# STLink_V3E_Module.net
KiCad netlist of a schematic drawn in Altium Designer
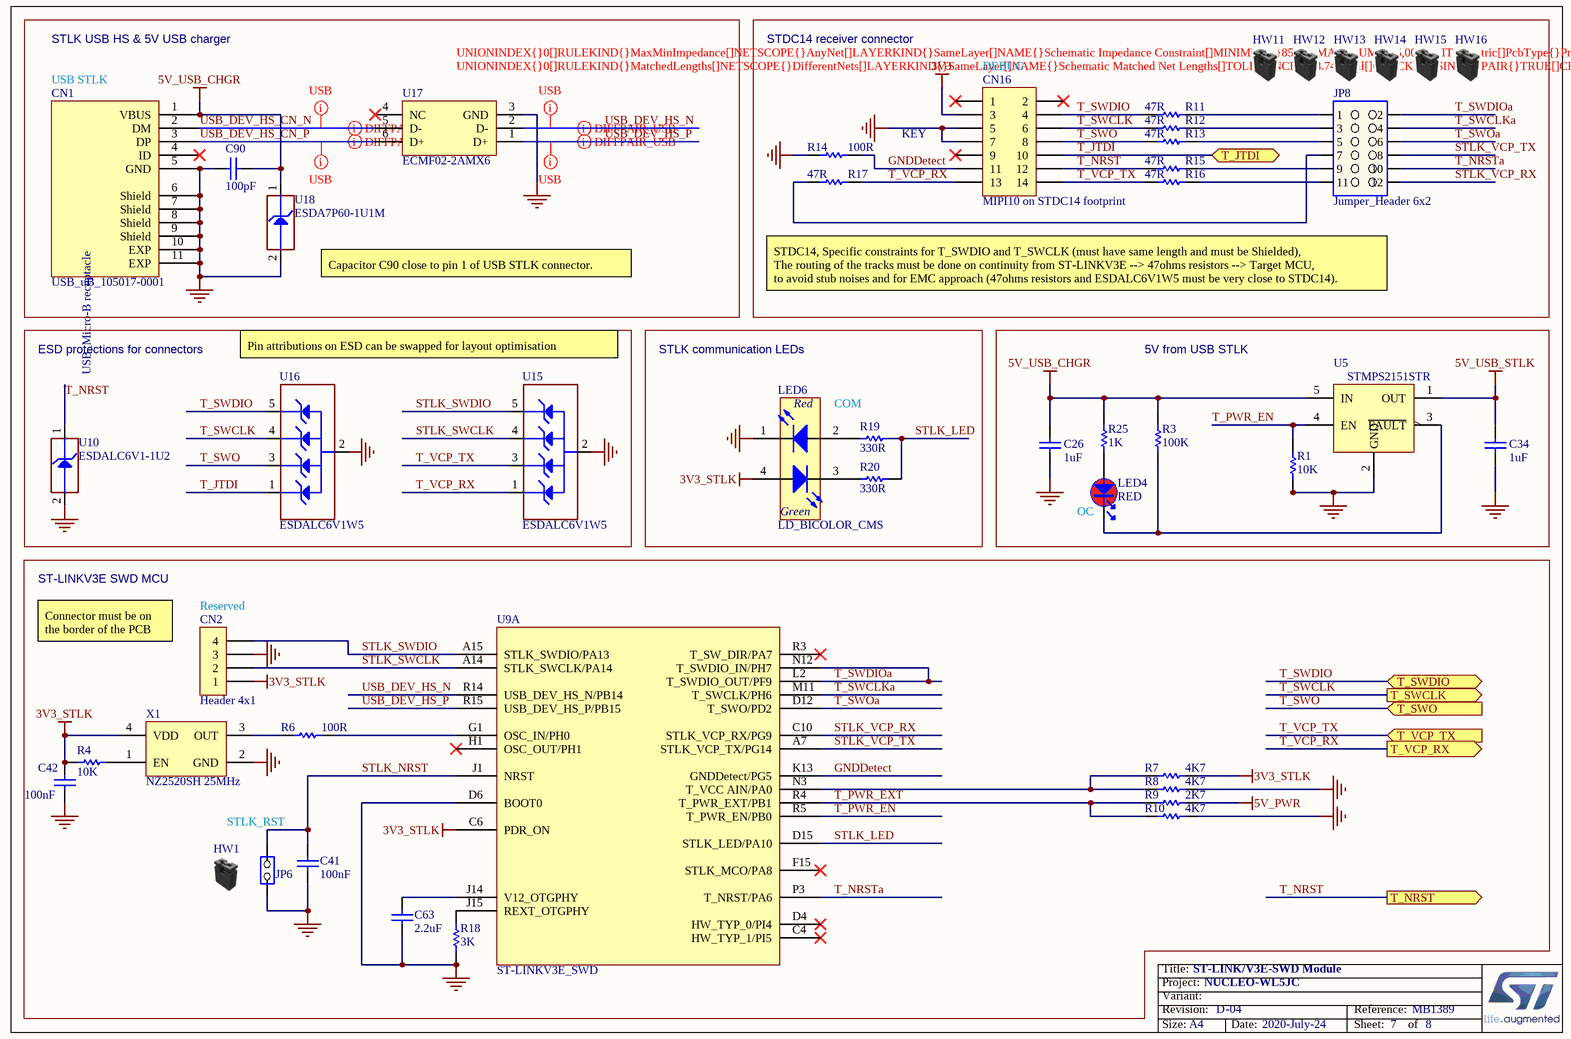
[diagram p0: STLink_V3E_Module.SchDoc]

(export (version "E")
  (design (tool "Eeschema 10.0.6"))
  (components
    (comp (ref "C26")
      (value "1uF")
      (footprint "C0603")
      (description "Capacitor, MLCC, 1uF, 16V, X5R, 10%, 0603, T=0,8mm")
      (fields
        (field (name "INTERNAL_PART_NUMBER") "MCD-00010")
        (field (name "MANUFACTURER_PART_NUMBER") "CC0603KRX5R7BB105")
        (field (name "PROVIDED_BY") "SUBCO")
      )
      (libsource (lib "MCD_PARTS_database") (part "Capacitor"))
    )
    (comp (ref "C34")
      (value "1uF")
      (footprint "C0603")
      (description "Capacitor, MLCC, 1uF, 16V, X5R, 10%, 0603, T=0,8mm")
      (fields
        (field (name "INTERNAL_PART_NUMBER") "MCD-00010")
        (field (name "MANUFACTURER_PART_NUMBER") "CC0603KRX5R7BB105")
        (field (name "PROVIDED_BY") "SUBCO")
      )
      (libsource (lib "MCD_PARTS_database") (part "Capacitor"))
    )
    (comp (ref "C41")
      (value "100nF")
      (footprint "C0402")
      (description "Capacitor, MLCC, 100nF, 16V, X7R, 10%, 0402, T=0,5mm")
      (fields
        (field (name "INTERNAL_PART_NUMBER") "MCD-00102")
        (field (name "MANUFACTURER_PART_NUMBER") "CC0402KRX7R7BB104")
        (field (name "PROVIDED_BY") "SUBCO")
      )
      (libsource (lib "MCD_PARTS_database") (part "Capacitor"))
    )
    (comp (ref "C42")
      (value "100nF")
      (footprint "C0402")
      (description "Capacitor, MLCC, 100nF, 16V, X7R, 10%, 0402, T=0,5mm")
      (fields
        (field (name "INTERNAL_PART_NUMBER") "MCD-00102")
        (field (name "MANUFACTURER_PART_NUMBER") "CC0402KRX7R7BB104")
        (field (name "PROVIDED_BY") "SUBCO")
      )
      (libsource (lib "MCD_PARTS_database") (part "Capacitor"))
    )
    (comp (ref "C63")
      (value "2.2uF")
      (footprint "C0603")
      (description "Capacitor, MLCC, 2.2uF, 10V, X5R, 10%, 0603, T=0,8mm")
      (fields
        (field (name "INTERNAL_PART_NUMBER") "MCD-00012")
        (field (name "MANUFACTURER_PART_NUMBER") "CC0603KRX5R6BB225")
        (field (name "PROVIDED_BY") "SUBCO")
      )
      (libsource (lib "MCD_PARTS_database") (part "Capacitor"))
    )
    (comp (ref "C90")
      (value "100pF")
      (footprint "C0402")
      (description "Capacitor, MLCC, 100pF, 50V, NPO, 5%, 0402, T=0,5mm")
      (fields
        (field (name "INTERNAL_PART_NUMBER") "MCD-00205")
        (field (name "MANUFACTURER_PART_NUMBER") "CC0402JRNPO9BN101")
        (field (name "PROVIDED_BY") "SUBCO")
      )
      (libsource (lib "MCD_PARTS_database") (part "Capacitor"))
    )
    (comp (ref "CN1")
      (value "USB_uB_105017-0001")
      (footprint "CON_USBMICROB_MOLEX_105017-0001_H2P90")
      (description "USB-MICRO-B, 0.65mm, RA, SMT, Bottom Mount,")
      (fields
        (field (name "INTERNAL_PART_NUMBER") "MCD-00028")
        (field (name "MANUFACTURER_PART_NUMBER") "1050170001")
        (field (name "PROVIDED_BY") "SUBCO")
      )
      (libsource (lib "MCD_PARTS_database") (part "USB_uB_105017.0001"))
    )
    (comp (ref "CN2")
      (value "Header 4x1")
      (footprint "CON_SAMTEC_TSW-104-07-G-S")
      (description "Header, 4x1, 2,54mm, VR, TH, Height 5.84mm/2.54mm")
      (fields
        (field (name "INTERNAL_PART_NUMBER") "MCD-00029")
        (field (name "MANUFACTURER_PART_NUMBER") "TSW-104-07-x-S")
        (field (name "PROVIDED_BY") "SUBCO")
      )
      (libsource (lib "MCD_PARTS_database") (part "Header 4x1"))
    )
    (comp (ref "CN16")
      (value "MIPI10 on STDC14 footprint")
      (footprint "CON_STDC14_Receiver_MEDIUM_WITH_MIPI10_3D")
      (fields
        (field (name "INTERNAL_PART_NUMBER") "MCD-01226")
        (field (name "MANUFACTURER_PART_NUMBER") "FTSH-105-01-L-DV-K")
        (field (name "MANUFACTURER") "SAMTEC")
        (field (name "PROVIDED_BY") "SUBCO")
      )
      (libsource (lib "MCD_PARTS_database") (part "Header 7x2"))
    )
    (comp (ref "HW1")
      (value "~")
      (description "SHUNT 2.54mm BLACK")
      (fields
        (field (name "INTERNAL_PART_NUMBER") "MCD-00043")
        (field (name "MANUFACTURER_PART_NUMBER") "SNT-100-BK-G")
        (field (name "PROVIDED_BY") "SUBCO")
      )
      (libsource (lib "MCD_PARTS_database") (part "Shunt Black 2.54mm"))
    )
    (comp (ref "HW11")
      (value "~")
      (description "SHUNT 2.54mm BLACK")
      (fields
        (field (name "INTERNAL_PART_NUMBER") "MCD-00043")
        (field (name "MANUFACTURER_PART_NUMBER") "SNT-100-BK-G")
        (field (name "PROVIDED_BY") "SUBCO")
      )
      (libsource (lib "MCD_PARTS_database") (part "Shunt Black 2.54mm"))
    )
    (comp (ref "HW12")
      (value "~")
      (description "SHUNT 2.54mm BLACK")
      (fields
        (field (name "INTERNAL_PART_NUMBER") "MCD-00043")
        (field (name "MANUFACTURER_PART_NUMBER") "SNT-100-BK-G")
        (field (name "PROVIDED_BY") "SUBCO")
      )
      (libsource (lib "MCD_PARTS_database") (part "Shunt Black 2.54mm"))
    )
    (comp (ref "HW13")
      (value "~")
      (description "SHUNT 2.54mm BLACK")
      (fields
        (field (name "INTERNAL_PART_NUMBER") "MCD-00043")
        (field (name "MANUFACTURER_PART_NUMBER") "SNT-100-BK-G")
        (field (name "PROVIDED_BY") "SUBCO")
      )
      (libsource (lib "MCD_PARTS_database") (part "Shunt Black 2.54mm"))
    )
    (comp (ref "HW14")
      (value "~")
      (description "SHUNT 2.54mm BLACK")
      (fields
        (field (name "INTERNAL_PART_NUMBER") "MCD-00043")
        (field (name "MANUFACTURER_PART_NUMBER") "SNT-100-BK-G")
        (field (name "PROVIDED_BY") "SUBCO")
      )
      (libsource (lib "MCD_PARTS_database") (part "Shunt Black 2.54mm"))
    )
    (comp (ref "HW15")
      (value "~")
      (description "SHUNT 2.54mm BLACK")
      (fields
        (field (name "INTERNAL_PART_NUMBER") "MCD-00043")
        (field (name "MANUFACTURER_PART_NUMBER") "SNT-100-BK-G")
        (field (name "PROVIDED_BY") "SUBCO")
      )
      (libsource (lib "MCD_PARTS_database") (part "Shunt Black 2.54mm"))
    )
    (comp (ref "HW16")
      (value "~")
      (description "SHUNT 2.54mm BLACK")
      (fields
        (field (name "INTERNAL_PART_NUMBER") "MCD-00043")
        (field (name "MANUFACTURER_PART_NUMBER") "SNT-100-BK-G")
        (field (name "PROVIDED_BY") "SUBCO")
      )
      (libsource (lib "MCD_PARTS_database") (part "Shunt Black 2.54mm"))
    )
    (comp (ref "JP6")
      (value "~")
      (footprint "CON_SAMTEC_TSW-102-07-G-S")
      (description "Header, 2x1, 2,54mm, VR, TH, Height 5.84mm/2.54mm")
      (fields
        (field (name "INTERNAL_PART_NUMBER") "MCD-00045")
        (field (name "MANUFACTURER_PART_NUMBER") "TSW-102-07-G-S")
        (field (name "PROVIDED_BY") "SUBCO")
      )
      (libsource (lib "MCD_PARTS_database") (part "Jumper_Header 2x1"))
    )
    (comp (ref "JP8")
      (value "Jumper_Header 6x2")
      (footprint "CON_SAMTEC_TSW-106-07-X-D")
      (description "Header, 6x2, 2,54mm, VR, TH, Height 5.84mm/2.54mm")
      (fields
        (field (name "INTERNAL_PART_NUMBER") "MCD-00692")
        (field (name "MANUFACTURER_PART_NUMBER") "TSW-106-07-x-D")
        (field (name "PROVIDED_BY") "SUBCO")
      )
      (libsource (lib "MCD_PARTS_database") (part "Jumper_Header 6x2"))
    )
    (comp (ref "LED4")
      (value "RED")
      (footprint "LED_0603_VISHAY_VLMS1300-GS08_RED_1A2K_H0P8")
      (description "LED Red, 0603 SMD, 2V Forward Voltage")
      (fields
        (field (name "INTERNAL_PART_NUMBER") "MCD-00587")
        (field (name "MANUFACTURER_PART_NUMBER") "VLMS1300-GS08")
        (field (name "PROVIDED_BY") "SUBCO")
      )
      (libsource (lib "MCD_PARTS_database") (part "LED_red"))
    )
    (comp (ref "LED6")
      (value "LD_BICOLOR_CMS")
      (footprint "LED_BI-GR_HSMF-A201-A00J1")
      (description "LED Bicolor")
      (fields
        (field (name "INTERNAL_PART_NUMBER") "MCD-00051")
        (field (name "MANUFACTURER_PART_NUMBER") "HSMF-A201-A00J1")
        (field (name "PROVIDED_BY") "SUBCO")
      )
      (libsource (lib "MCD_PARTS_database") (part "LD_BICOLOR_CMS"))
    )
    (comp (ref "R1")
      (value "10K")
      (footprint "R0402")
      (description "Resistor,10K,0402,1%,1/16W")
      (fields
        (field (name "INTERNAL_PART_NUMBER") "MCD-00053")
        (field (name "MANUFACTURER_PART_NUMBER") "RC0402FR-0710KL")
        (field (name "PROVIDED_BY") "SUBCO")
      )
      (libsource (lib "MCD_PARTS_database") (part "Resistor"))
    )
    (comp (ref "R3")
      (value "100K")
      (footprint "R0402")
      (description "Resistor,100K,0402,1%,1/16W")
      (fields
        (field (name "INTERNAL_PART_NUMBER") "MCD-00059")
        (field (name "MANUFACTURER_PART_NUMBER") "RC0402FR-07100KL")
        (field (name "PROVIDED_BY") "SUBCO")
      )
      (libsource (lib "MCD_PARTS_database") (part "Resistor"))
    )
    (comp (ref "R4")
      (value "10K")
      (footprint "R0402")
      (description "Resistor,10K,0402,1%,1/16W")
      (fields
        (field (name "INTERNAL_PART_NUMBER") "MCD-00053")
        (field (name "MANUFACTURER_PART_NUMBER") "RC0402FR-0710KL")
        (field (name "PROVIDED_BY") "SUBCO")
      )
      (libsource (lib "MCD_PARTS_database") (part "Resistor"))
    )
    (comp (ref "R6")
      (value "100R")
      (footprint "R0402")
      (description "Resistor,100R,0402,1%,1/16W")
      (fields
        (field (name "INTERNAL_PART_NUMBER") "MCD-00119")
        (field (name "MANUFACTURER_PART_NUMBER") "RC0402FR-07100RL")
        (field (name "PROVIDED_BY") "SUBCO")
      )
      (libsource (lib "MCD_PARTS_database") (part "Resistor"))
    )
    (comp (ref "R7")
      (value "4K7")
      (footprint "R0402")
      (description "Resistor,4K7,0402,1%,1/16W")
      (fields
        (field (name "INTERNAL_PART_NUMBER") "MCD-00065")
        (field (name "MANUFACTURER_PART_NUMBER") "RC0402FR-074K7L")
        (field (name "PROVIDED_BY") "SUBCO")
      )
      (libsource (lib "MCD_PARTS_database") (part "Resistor"))
    )
    (comp (ref "R8")
      (value "4K7")
      (footprint "R0402")
      (description "Resistor,4K7,0402,1%,1/16W")
      (fields
        (field (name "INTERNAL_PART_NUMBER") "MCD-00065")
        (field (name "MANUFACTURER_PART_NUMBER") "RC0402FR-074K7L")
        (field (name "PROVIDED_BY") "SUBCO")
      )
      (libsource (lib "MCD_PARTS_database") (part "Resistor"))
    )
    (comp (ref "R9")
      (value "2K7")
      (footprint "R0402")
      (description "Resistor,2K7,0402,1%,1/16W")
      (fields
        (field (name "INTERNAL_PART_NUMBER") "MCD-00055")
        (field (name "MANUFACTURER_PART_NUMBER") "RC0402FR-072K7L")
        (field (name "PROVIDED_BY") "SUBCO")
      )
      (libsource (lib "MCD_PARTS_database") (part "Resistor"))
    )
    (comp (ref "R10")
      (value "4K7")
      (footprint "R0402")
      (description "Resistor,4K7,0402,1%,1/16W")
      (fields
        (field (name "INTERNAL_PART_NUMBER") "MCD-00065")
        (field (name "MANUFACTURER_PART_NUMBER") "RC0402FR-074K7L")
        (field (name "PROVIDED_BY") "SUBCO")
      )
      (libsource (lib "MCD_PARTS_database") (part "Resistor"))
    )
    (comp (ref "R11")
      (value "47R")
      (footprint "R0402")
      (description "Resistor,47R,0402,1%,1/16W")
      (fields
        (field (name "INTERNAL_PART_NUMBER") "MCD-00481")
        (field (name "MANUFACTURER_PART_NUMBER") "RC0402FR-0747RL")
        (field (name "PROVIDED_BY") "SUBCO")
      )
      (libsource (lib "MCD_PARTS_database") (part "Resistor"))
    )
    (comp (ref "R12")
      (value "47R")
      (footprint "R0402")
      (description "Resistor,47R,0402,1%,1/16W")
      (fields
        (field (name "INTERNAL_PART_NUMBER") "MCD-00481")
        (field (name "MANUFACTURER_PART_NUMBER") "RC0402FR-0747RL")
        (field (name "PROVIDED_BY") "SUBCO")
      )
      (libsource (lib "MCD_PARTS_database") (part "Resistor"))
    )
    (comp (ref "R13")
      (value "47R")
      (footprint "R0402")
      (description "Resistor,47R,0402,1%,1/16W")
      (fields
        (field (name "INTERNAL_PART_NUMBER") "MCD-00481")
        (field (name "MANUFACTURER_PART_NUMBER") "RC0402FR-0747RL")
        (field (name "PROVIDED_BY") "SUBCO")
      )
      (libsource (lib "MCD_PARTS_database") (part "Resistor"))
    )
    (comp (ref "R14")
      (value "100R")
      (footprint "R0402")
      (description "Resistor,100R,0402,1%,1/16W")
      (fields
        (field (name "INTERNAL_PART_NUMBER") "MCD-00119")
        (field (name "MANUFACTURER_PART_NUMBER") "RC0402FR-07100RL")
        (field (name "PROVIDED_BY") "SUBCO")
      )
      (libsource (lib "MCD_PARTS_database") (part "Resistor"))
    )
    (comp (ref "R15")
      (value "47R")
      (footprint "R0402")
      (description "Resistor,47R,0402,1%,1/16W")
      (fields
        (field (name "INTERNAL_PART_NUMBER") "MCD-00481")
        (field (name "MANUFACTURER_PART_NUMBER") "RC0402FR-0747RL")
        (field (name "PROVIDED_BY") "SUBCO")
      )
      (libsource (lib "MCD_PARTS_database") (part "Resistor"))
    )
    (comp (ref "R16")
      (value "47R")
      (footprint "R0402")
      (description "Resistor,47R,0402,1%,1/16W")
      (fields
        (field (name "INTERNAL_PART_NUMBER") "MCD-00481")
        (field (name "MANUFACTURER_PART_NUMBER") "RC0402FR-0747RL")
        (field (name "PROVIDED_BY") "SUBCO")
      )
      (libsource (lib "MCD_PARTS_database") (part "Resistor"))
    )
    (comp (ref "R17")
      (value "47R")
      (footprint "R0402")
      (description "Resistor,47R,0402,1%,1/16W")
      (fields
        (field (name "INTERNAL_PART_NUMBER") "MCD-00481")
        (field (name "MANUFACTURER_PART_NUMBER") "RC0402FR-0747RL")
        (field (name "PROVIDED_BY") "SUBCO")
      )
      (libsource (lib "MCD_PARTS_database") (part "Resistor"))
    )
    (comp (ref "R18")
      (value "3K")
      (footprint "R0402")
      (description "Resistor,3K,0402,1%,1/16W")
      (fields
        (field (name "INTERNAL_PART_NUMBER") "MCD-00185")
        (field (name "MANUFACTURER_PART_NUMBER") "RC0402FR-073KL")
        (field (name "PROVIDED_BY") "SUBCO")
      )
      (libsource (lib "MCD_PARTS_database") (part "Resistor"))
    )
    (comp (ref "R19")
      (value "330R")
      (footprint "R0603")
      (description "Resistor,330R,0603,1%,1/10W")
      (fields
        (field (name "INTERNAL_PART_NUMBER") "MCD-00197")
        (field (name "MANUFACTURER_PART_NUMBER") "RC0603FR-07330RL")
        (field (name "PROVIDED_BY") "SUBCO")
      )
      (libsource (lib "MCD_PARTS_database") (part "Resistor"))
    )
    (comp (ref "R20")
      (value "330R")
      (footprint "R0603")
      (description "Resistor,330R,0603,1%,1/10W")
      (fields
        (field (name "INTERNAL_PART_NUMBER") "MCD-00197")
        (field (name "MANUFACTURER_PART_NUMBER") "RC0603FR-07330RL")
        (field (name "PROVIDED_BY") "SUBCO")
      )
      (libsource (lib "MCD_PARTS_database") (part "Resistor"))
    )
    (comp (ref "R25")
      (value "1K")
      (footprint "R0603")
      (description "Resistor,1K,0603,1%,1/10W")
      (fields
        (field (name "INTERNAL_PART_NUMBER") "MCD-00070")
        (field (name "MANUFACTURER_PART_NUMBER") "RC0603FR-071KL")
        (field (name "PROVIDED_BY") "SUBCO")
      )
      (libsource (lib "MCD_PARTS_database") (part "Resistor"))
    )
    (comp (ref "U5")
      (value "STMPS2151STR")
      (footprint "MOS_SOT23-5L")
      (description "500mA, Enhanced single channel power switches with active high enable pin")
      (fields
        (field (name "INTERNAL_PART_NUMBER") "MCD-00159")
        (field (name "MANUFACTURER") "STMICROELECTRONICS")
        (field (name "PROVIDED_BY") "SUBCO with ST control")
      )
      (libsource (lib "MCD_PARTS_database") (part "STMPS2151STR"))
    )
    (comp (ref "U9")
      (value "ST-LINKV3E_SWD")
      (footprint "ICC_UFBGA201_176+25_10X10_P065")
      (description "STM32F723IEK  (STM32F7) BGA176")
      (fields
        (field (name "INTERNAL_PART_NUMBER") "MCD-00596")
        (field (name "MANUFACTURER_PART_NUMBER") "STM32F723IEK6")
        (field (name "PROVIDED_BY") "SUBCO with ST control")
      )
      (libsource (lib "MCD_PARTS_database") (part "ST-LINKV3E_SWD"))
    )
    (comp (ref "U10")
      (value "ESDALC6V1-1U2")
      (footprint "ESD_ST0201")
      (description "ESD protection 6V1")
      (fields
        (field (name "INTERNAL_PART_NUMBER") "MCD-00170")
        (field (name "MANUFACTURER") "STMICROELECTRONICS")
        (field (name "PROVIDED_BY") "SUBCO with ST control")
      )
      (libsource (lib "MCD_PARTS_database") (part "ESD-TRANSIL"))
    )
    (comp (ref "U15")
      (value "ESDALC6V1W5")
      (footprint "ESD_SOT323-5L")
      (description "Dual Transil array for ESD protection")
      (fields
        (field (name "INTERNAL_PART_NUMBER") "MCD-00136")
        (field (name "MANUFACTURER") "STMICROELECTRONICS")
        (field (name "PROVIDED_BY") "SUBCO with ST control")
      )
      (libsource (lib "MCD_PARTS_database") (part "ESDALC6V1W5"))
    )
    (comp (ref "U16")
      (value "ESDALC6V1W5")
      (footprint "ESD_SOT323-5L")
      (description "Dual Transil array for ESD protection")
      (fields
        (field (name "INTERNAL_PART_NUMBER") "MCD-00136")
        (field (name "MANUFACTURER") "STMICROELECTRONICS")
        (field (name "PROVIDED_BY") "SUBCO with ST control")
      )
      (libsource (lib "MCD_PARTS_database") (part "ESDALC6V1W5"))
    )
    (comp (ref "U17")
      (value "ECMF02-2AMX6")
      (footprint "ESD_QFN-6L_1P7X1P5_P050")
      (description "Common mode filter with ESD protection for USB 2.0 interface")
      (fields
        (field (name "INTERNAL_PART_NUMBER") "MCD-00649")
        (field (name "MANUFACTURER") "STMICROELECTRONICS")
        (field (name "PROVIDED_BY") "SUBCO with ST control")
      )
      (libsource (lib "MCD_PARTS_database") (part "ECMF02-2AMX6"))
    )
    (comp (ref "U18")
      (value "ESDA7P60-1U1M")
      (footprint "ESD_QFN2_1P6X1_P125")
      (description "High power transient voltage suppressor, 7V breakdown")
      (fields
        (field (name "INTERNAL_PART_NUMBER") "MCD-00251")
        (field (name "MANUFACTURER") "STMICROELECTRONICS")
        (field (name "PROVIDED_BY") "SUBCO with ST control")
      )
      (libsource (lib "MCD_PARTS_database") (part "ESD-TRANSIL"))
    )
    (comp (ref "X1")
      (value "NZ2520SH 25MHz")
      (footprint "OSC_NDK_NZ2520SB_4P")
      (description "Oscillator 25Mhz, +-50ppm, Vcc:3.3V typ, square wave: [0.1Vcc;0.9Vcc], Enable pin, SMD")
      (fields
        (field (name "INTERNAL_PART_NUMBER") "MCD-00597")
        (field (name "MANUFACTURER_PART_NUMBER") "NZ2520SH 25MHz END4869C")
        (field (name "PROVIDED_BY") "SUBCO")
      )
      (libsource (lib "MCD_PARTS_database") (part "OSCILLATOR_4_PINS"))
    )
  )
  (nets
    (net (code "1") (name "/GNDDetect") (class "Default")
      (node (ref "CN16") (pin "11") (pinfunction "11_11") (pintype "passive"))
      (node (ref "R14") (pin "2") (pinfunction "2_2") (pintype "passive"))
      (node (ref "U9") (pin "K13") (pinfunction "GNDDetect/PG5_K13") (pintype "passive"))
    )
    (net (code "2") (name "/STLK_LED") (class "Default")
      (node (ref "R19") (pin "2") (pinfunction "2_2") (pintype "passive"))
      (node (ref "R20") (pin "2") (pinfunction "2_2") (pintype "passive"))
      (node (ref "U9") (pin "D15") (pinfunction "STLK_LED/PA10_D15") (pintype "passive"))
    )
    (net (code "3") (name "/STLK_NRST") (class "Default")
      (node (ref "C41") (pin "2") (pinfunction "2_2") (pintype "passive"))
      (node (ref "JP6") (pin "2") (pinfunction "NO_2") (pintype "passive"))
      (node (ref "U9") (pin "J1") (pinfunction "NRST_J1") (pintype "passive"))
    )
    (net (code "4") (name "/STLK_SWCLK") (class "Default")
      (node (ref "CN2") (pin "2") (pinfunction "2_2") (pintype "passive"))
      (node (ref "U15") (pin "4") (pinfunction "IO3_4") (pintype "passive"))
      (node (ref "U9") (pin "A14") (pinfunction "STLK_SWCLK/PA14_A14") (pintype "passive"))
    )
    (net (code "5") (name "/STLK_SWDIO") (class "Default")
      (node (ref "CN2") (pin "4") (pinfunction "4_4") (pintype "passive"))
      (node (ref "U15") (pin "5") (pinfunction "IO4_5") (pintype "passive"))
      (node (ref "U9") (pin "A15") (pinfunction "STLK_SWDIO/PA13_A15") (pintype "passive"))
    )
    (net (code "6") (name "/STLK_VCP_RX") (class "Default")
      (node (ref "JP8") (pin "12") (pinfunction "12_12") (pintype "passive"))
      (node (ref "U9") (pin "C10") (pinfunction "STLK_VCP_RX/PG9_C10") (pintype "passive"))
    )
    (net (code "7") (name "/STLK_VCP_TX") (class "Default")
      (node (ref "JP8") (pin "8") (pinfunction "8_8") (pintype "passive"))
      (node (ref "U9") (pin "A7") (pinfunction "STLK_VCP_TX/PG14_A7") (pintype "passive"))
    )
    (net (code "8") (name "/T_JTDI") (class "Default")
      (node (ref "CN16") (pin "10") (pinfunction "10_10") (pintype "passive"))
      (node (ref "U16") (pin "1") (pinfunction "IO1_1") (pintype "passive"))
    )
    (net (code "9") (name "/T_NRST") (class "Default")
      (node (ref "CN16") (pin "12") (pinfunction "12_12") (pintype "passive"))
      (node (ref "R15") (pin "1") (pinfunction "1_1") (pintype "passive"))
      (node (ref "U10") (pin "1") (pinfunction "IO1_1") (pintype "passive"))
    )
    (net (code "10") (name "/T_NRSTa") (class "Default")
      (node (ref "JP8") (pin "10") (pinfunction "10_10") (pintype "passive"))
      (node (ref "U9") (pin "P3") (pinfunction "T_NRST/PA6_P3") (pintype "passive"))
    )
    (net (code "11") (name "/T_PWR_EN") (class "Default")
      (node (ref "R1") (pin "2") (pinfunction "2_2") (pintype "passive"))
      (node (ref "U5") (pin "4") (pinfunction "EN_4") (pintype "passive"))
      (node (ref "U9") (pin "R5") (pinfunction "T_PWR_EN/PB0_R5") (pintype "passive"))
    )
    (net (code "12") (name "/T_PWR_EXT") (class "Default")
      (node (ref "R10") (pin "2") (pinfunction "2_2") (pintype "passive"))
      (node (ref "R9") (pin "2") (pinfunction "2_2") (pintype "passive"))
      (node (ref "U9") (pin "R4") (pinfunction "T_PWR_EXT/PB1_R4") (pintype "passive"))
    )
    (net (code "13") (name "/T_SWCLK") (class "Default")
      (node (ref "CN16") (pin "6") (pinfunction "6_6") (pintype "passive"))
      (node (ref "R12") (pin "1") (pinfunction "1_1") (pintype "passive"))
      (node (ref "U16") (pin "4") (pinfunction "IO3_4") (pintype "passive"))
    )
    (net (code "14") (name "/T_SWCLKa") (class "Default")
      (node (ref "JP8") (pin "4") (pinfunction "4_4") (pintype "passive"))
      (node (ref "U9") (pin "M11") (pinfunction "T_SWCLK/PH6_M11") (pintype "passive"))
    )
    (net (code "15") (name "/T_SWDIO") (class "Default")
      (node (ref "CN16") (pin "4") (pinfunction "4_4") (pintype "passive"))
      (node (ref "R11") (pin "1") (pinfunction "1_1") (pintype "passive"))
      (node (ref "U16") (pin "5") (pinfunction "IO4_5") (pintype "passive"))
    )
    (net (code "16") (name "/T_SWDIOa") (class "Default")
      (node (ref "JP8") (pin "2") (pinfunction "2_2") (pintype "passive"))
      (node (ref "U9") (pin "L2") (pinfunction "T_SWDIO_OUT/PF9_L2") (pintype "passive"))
      (node (ref "U9") (pin "N12") (pinfunction "T_SWDIO_IN/PH7_N12") (pintype "passive"))
    )
    (net (code "17") (name "/T_SWO") (class "Default")
      (node (ref "CN16") (pin "8") (pinfunction "8_8") (pintype "passive"))
      (node (ref "R13") (pin "1") (pinfunction "1_1") (pintype "passive"))
      (node (ref "U16") (pin "3") (pinfunction "IO2_3") (pintype "passive"))
    )
    (net (code "18") (name "/T_SWOa") (class "Default")
      (node (ref "JP8") (pin "6") (pinfunction "6_6") (pintype "passive"))
      (node (ref "U9") (pin "D12") (pinfunction "T_SWO/PD2_D12") (pintype "passive"))
    )
    (net (code "19") (name "/T_VCP_RX") (class "Default")
      (node (ref "CN16") (pin "13") (pinfunction "13_13") (pintype "passive"))
      (node (ref "R17") (pin "2") (pinfunction "2_2") (pintype "passive"))
      (node (ref "U15") (pin "1") (pinfunction "IO1_1") (pintype "passive"))
    )
    (net (code "20") (name "/T_VCP_TX") (class "Default")
      (node (ref "CN16") (pin "14") (pinfunction "14_14") (pintype "passive"))
      (node (ref "R16") (pin "1") (pinfunction "1_1") (pintype "passive"))
      (node (ref "U15") (pin "3") (pinfunction "IO2_3") (pintype "passive"))
    )
    (net (code "21") (name "/USB_DEV_HS_CN_N") (class "Default")
      (node (ref "CN1") (pin "2") (pinfunction "DM_2") (pintype "passive"))
      (node (ref "U17") (pin "5") (pinfunction "D-_5") (pintype "passive"))
    )
    (net (code "22") (name "/USB_DEV_HS_CN_P") (class "Default")
      (node (ref "CN1") (pin "3") (pinfunction "DP_3") (pintype "passive"))
      (node (ref "U17") (pin "6") (pinfunction "D+_6") (pintype "passive"))
    )
    (net (code "23") (name "/USB_DEV_HS_N") (class "Default")
      (node (ref "U17") (pin "2") (pinfunction "D-_2") (pintype "passive"))
      (node (ref "U9") (pin "R14") (pinfunction "USB_DEV_HS_N/PB14_R14") (pintype "passive"))
    )
    (net (code "24") (name "/USB_DEV_HS_P") (class "Default")
      (node (ref "U17") (pin "1") (pinfunction "D+_1") (pintype "passive"))
      (node (ref "U9") (pin "R15") (pinfunction "USB_DEV_HS_P/PB15_R15") (pintype "passive"))
    )
    (net (code "25") (name "3V3") (class "Default")
      (node (ref "CN16") (pin "3") (pinfunction "3_3") (pintype "passive"))
    )
    (net (code "26") (name "3V3_STLK") (class "Default")
      (node (ref "C42") (pin "2") (pinfunction "2_2") (pintype "passive"))
      (node (ref "CN2") (pin "1") (pinfunction "1_1") (pintype "passive"))
      (node (ref "LED6") (pin "4") (pinfunction "YellowGreen_anode_4") (pintype "passive"))
      (node (ref "R4") (pin "1") (pinfunction "1_1") (pintype "passive"))
      (node (ref "R7") (pin "1") (pinfunction "1_1") (pintype "passive"))
      (node (ref "U9") (pin "C6") (pinfunction "PDR_ON_C6") (pintype "passive"))
      (node (ref "X1") (pin "4") (pinfunction "VDD_4") (pintype "passive"))
    )
    (net (code "27") (name "5V_PWR") (class "Default")
      (node (ref "R9") (pin "1") (pinfunction "1_1") (pintype "passive"))
    )
    (net (code "28") (name "5V_USB_CHGR") (class "Default")
      (node (ref "C26") (pin "2") (pinfunction "2_2") (pintype "passive"))
      (node (ref "C90") (pin "2") (pinfunction "2_2") (pintype "passive"))
      (node (ref "CN1") (pin "1") (pinfunction "VBUS_1") (pintype "passive"))
      (node (ref "R25") (pin "2") (pinfunction "2_2") (pintype "passive"))
      (node (ref "R3") (pin "2") (pinfunction "2_2") (pintype "passive"))
      (node (ref "U18") (pin "1") (pinfunction "IO1_1") (pintype "passive"))
      (node (ref "U5") (pin "5") (pinfunction "IN_5") (pintype "passive"))
    )
    (net (code "29") (name "5V_USB_STLK") (class "Default")
      (node (ref "C34") (pin "2") (pinfunction "2_2") (pintype "passive"))
      (node (ref "U5") (pin "1") (pinfunction "OUT_1") (pintype "passive"))
    )
    (net (code "30") (name "GND") (class "Default")
      (node (ref "C26") (pin "1") (pinfunction "1_1") (pintype "passive"))
      (node (ref "C34") (pin "1") (pinfunction "1_1") (pintype "passive"))
      (node (ref "C41") (pin "1") (pinfunction "1_1") (pintype "passive"))
      (node (ref "C42") (pin "1") (pinfunction "1_1") (pintype "passive"))
      (node (ref "C63") (pin "1") (pinfunction "1_1") (pintype "passive"))
      (node (ref "C90") (pin "1") (pinfunction "1_1") (pintype "passive"))
      (node (ref "CN1") (pin "10") (pinfunction "EXP_10") (pintype "passive"))
      (node (ref "CN1") (pin "11") (pinfunction "EXP_11") (pintype "passive"))
      (node (ref "CN1") (pin "5") (pinfunction "GND_5") (pintype "passive"))
      (node (ref "CN1") (pin "6") (pinfunction "Shield_6") (pintype "passive"))
      (node (ref "CN1") (pin "7") (pinfunction "Shield_7") (pintype "passive"))
      (node (ref "CN1") (pin "8") (pinfunction "Shield_8") (pintype "passive"))
      (node (ref "CN1") (pin "9") (pinfunction "Shield_9") (pintype "passive"))
      (node (ref "CN16") (pin "5") (pinfunction "5_5") (pintype "passive"))
      (node (ref "CN16") (pin "7") (pinfunction "7_7") (pintype "passive"))
      (node (ref "CN2") (pin "3") (pinfunction "3_3") (pintype "passive"))
      (node (ref "JP6") (pin "1") (pinfunction "COMMON_1") (pintype "passive"))
      (node (ref "LED6") (pin "1") (pinfunction "RED_cathode_1") (pintype "passive"))
      (node (ref "R1") (pin "1") (pinfunction "1_1") (pintype "passive"))
      (node (ref "R10") (pin "1") (pinfunction "1_1") (pintype "passive"))
      (node (ref "R14") (pin "1") (pinfunction "1_1") (pintype "passive"))
      (node (ref "R18") (pin "1") (pinfunction "1_1") (pintype "passive"))
      (node (ref "R8") (pin "1") (pinfunction "1_1") (pintype "passive"))
      (node (ref "U10") (pin "2") (pinfunction "GND_2") (pintype "passive"))
      (node (ref "U15") (pin "2") (pinfunction "GND_2") (pintype "passive"))
      (node (ref "U16") (pin "2") (pinfunction "GND_2") (pintype "passive"))
      (node (ref "U17") (pin "3") (pinfunction "GND_3") (pintype "passive"))
      (node (ref "U18") (pin "2") (pinfunction "GND_2") (pintype "passive"))
      (node (ref "U5") (pin "2") (pinfunction "GND_2") (pintype "passive"))
      (node (ref "U9") (pin "D6") (pinfunction "BOOT0_D6") (pintype "passive"))
      (node (ref "X1") (pin "2") (pinfunction "GND_2") (pintype "passive"))
    )
    (net (code "31") (name "Net-(JP8-Pad1)") (class "Default")
      (node (ref "JP8") (pin "1") (pinfunction "1_1") (pintype "passive"))
      (node (ref "R11") (pin "2") (pinfunction "2_2") (pintype "passive"))
    )
    (net (code "32") (name "Net-(JP8-Pad3)") (class "Default")
      (node (ref "JP8") (pin "3") (pinfunction "3_3") (pintype "passive"))
      (node (ref "R12") (pin "2") (pinfunction "2_2") (pintype "passive"))
    )
    (net (code "33") (name "Net-(JP8-Pad5)") (class "Default")
      (node (ref "JP8") (pin "5") (pinfunction "5_5") (pintype "passive"))
      (node (ref "R13") (pin "2") (pinfunction "2_2") (pintype "passive"))
    )
    (net (code "34") (name "Net-(JP8-Pad7)") (class "Default")
      (node (ref "JP8") (pin "7") (pinfunction "7_7") (pintype "passive"))
      (node (ref "R17") (pin "1") (pinfunction "1_1") (pintype "passive"))
    )
    (net (code "35") (name "Net-(JP8-Pad9)") (class "Default")
      (node (ref "JP8") (pin "9") (pinfunction "9_9") (pintype "passive"))
      (node (ref "R15") (pin "2") (pinfunction "2_2") (pintype "passive"))
    )
    (net (code "36") (name "Net-(JP8-Pad11)") (class "Default")
      (node (ref "JP8") (pin "11") (pinfunction "11_11") (pintype "passive"))
      (node (ref "R16") (pin "2") (pinfunction "2_2") (pintype "passive"))
    )
    (net (code "37") (name "Net-(LED4-Pad1)") (class "Default")
      (node (ref "LED4") (pin "1") (pintype "passive"))
      (node (ref "R25") (pin "1") (pinfunction "1_1") (pintype "passive"))
    )
    (net (code "38") (name "Net-(LED6-Red_anode)") (class "Default")
      (node (ref "LED6") (pin "2") (pinfunction "Red_anode_2") (pintype "passive"))
      (node (ref "R19") (pin "1") (pinfunction "1_1") (pintype "passive"))
    )
    (net (code "39") (name "Net-(LED6-YellowGreen_cathode)") (class "Default")
      (node (ref "LED6") (pin "3") (pinfunction "YellowGreen_cathode_3") (pintype "passive"))
      (node (ref "R20") (pin "1") (pinfunction "1_1") (pintype "passive"))
    )
    (net (code "40") (name "Net-(U5-~{FAULT})") (class "Default")
      (node (ref "LED4") (pin "2") (pintype "passive"))
      (node (ref "R3") (pin "1") (pinfunction "1_1") (pintype "passive"))
      (node (ref "U5") (pin "3") (pinfunction "~{FAULT}_3") (pintype "passive"))
    )
    (net (code "41") (name "Net-(U9A-OSC_IN{slash}PH0)") (class "Default")
      (node (ref "R6") (pin "2") (pinfunction "2_2") (pintype "passive"))
      (node (ref "U9") (pin "G1") (pinfunction "OSC_IN/PH0_G1") (pintype "passive"))
    )
    (net (code "42") (name "Net-(U9A-REXT_OTGPHY)") (class "Default")
      (node (ref "R18") (pin "2") (pinfunction "2_2") (pintype "passive"))
      (node (ref "U9") (pin "J15") (pinfunction "REXT_OTGPHY_J15") (pintype "passive"))
    )
    (net (code "43") (name "Net-(U9A-T_VCC_AIN{slash}PA0)") (class "Default")
      (node (ref "R7") (pin "2") (pinfunction "2_2") (pintype "passive"))
      (node (ref "R8") (pin "2") (pinfunction "2_2") (pintype "passive"))
      (node (ref "U9") (pin "N3") (pinfunction "T_VCC_AIN/PA0_N3") (pintype "passive"))
    )
    (net (code "44") (name "Net-(U9A-V12_OTGPHY)") (class "Default")
      (node (ref "C63") (pin "2") (pinfunction "2_2") (pintype "passive"))
      (node (ref "U9") (pin "J14") (pinfunction "V12_OTGPHY_J14") (pintype "passive"))
    )
    (net (code "45") (name "Net-(X1-EN)") (class "Default")
      (node (ref "R4") (pin "2") (pinfunction "2_2") (pintype "passive"))
      (node (ref "X1") (pin "1") (pinfunction "EN_1") (pintype "passive"))
    )
    (net (code "46") (name "Net-(X1-OUT)") (class "Default")
      (node (ref "R6") (pin "1") (pinfunction "1_1") (pintype "passive"))
      (node (ref "X1") (pin "3") (pinfunction "OUT_3") (pintype "passive"))
    )
    (net (code "47") (name "unconnected-(CN1-ID-Pad4)") (class "Default")
      (node (ref "CN1") (pin "4") (pinfunction "ID_4") (pintype "passive+no_connect"))
    )
    (net (code "48") (name "unconnected-(CN16-Pad1)") (class "Default")
      (node (ref "CN16") (pin "1") (pinfunction "1_1") (pintype "passive+no_connect"))
    )
    (net (code "49") (name "unconnected-(CN16-Pad2)") (class "Default")
      (node (ref "CN16") (pin "2") (pinfunction "2_2") (pintype "passive+no_connect"))
    )
    (net (code "50") (name "unconnected-(CN16-Pad9)") (class "Default")
      (node (ref "CN16") (pin "9") (pinfunction "9_9") (pintype "passive+no_connect"))
    )
    (net (code "51") (name "unconnected-(U9A-HW_TYP_0{slash}PI4-PadD4)") (class "Default")
      (node (ref "U9") (pin "D4") (pinfunction "HW_TYP_0/PI4_D4") (pintype "passive+no_connect"))
    )
    (net (code "52") (name "unconnected-(U9A-HW_TYP_1{slash}PI5-PadC4)") (class "Default")
      (node (ref "U9") (pin "C4") (pinfunction "HW_TYP_1/PI5_C4") (pintype "passive+no_connect"))
    )
    (net (code "53") (name "unconnected-(U9A-OSC_OUT{slash}PH1-PadH1)") (class "Default")
      (node (ref "U9") (pin "H1") (pinfunction "OSC_OUT/PH1_H1") (pintype "passive+no_connect"))
    )
    (net (code "54") (name "unconnected-(U9A-STLK_MCO{slash}PA8-PadF15)") (class "Default")
      (node (ref "U9") (pin "F15") (pinfunction "STLK_MCO/PA8_F15") (pintype "passive+no_connect"))
    )
    (net (code "55") (name "unconnected-(U9A-T_SW_DIR{slash}PA7-PadR3)") (class "Default")
      (node (ref "U9") (pin "R3") (pinfunction "T_SW_DIR/PA7_R3") (pintype "passive+no_connect"))
    )
    (net (code "56") (name "unconnected-(U17-NC-Pad4)") (class "Default")
      (node (ref "U17") (pin "4") (pinfunction "NC_4") (pintype "passive+no_connect"))
    )
  )
)
